# P8_CCD_CAM_BOARD_COMM.net
KiCad netlist of a schematic drawn in Altium Designer
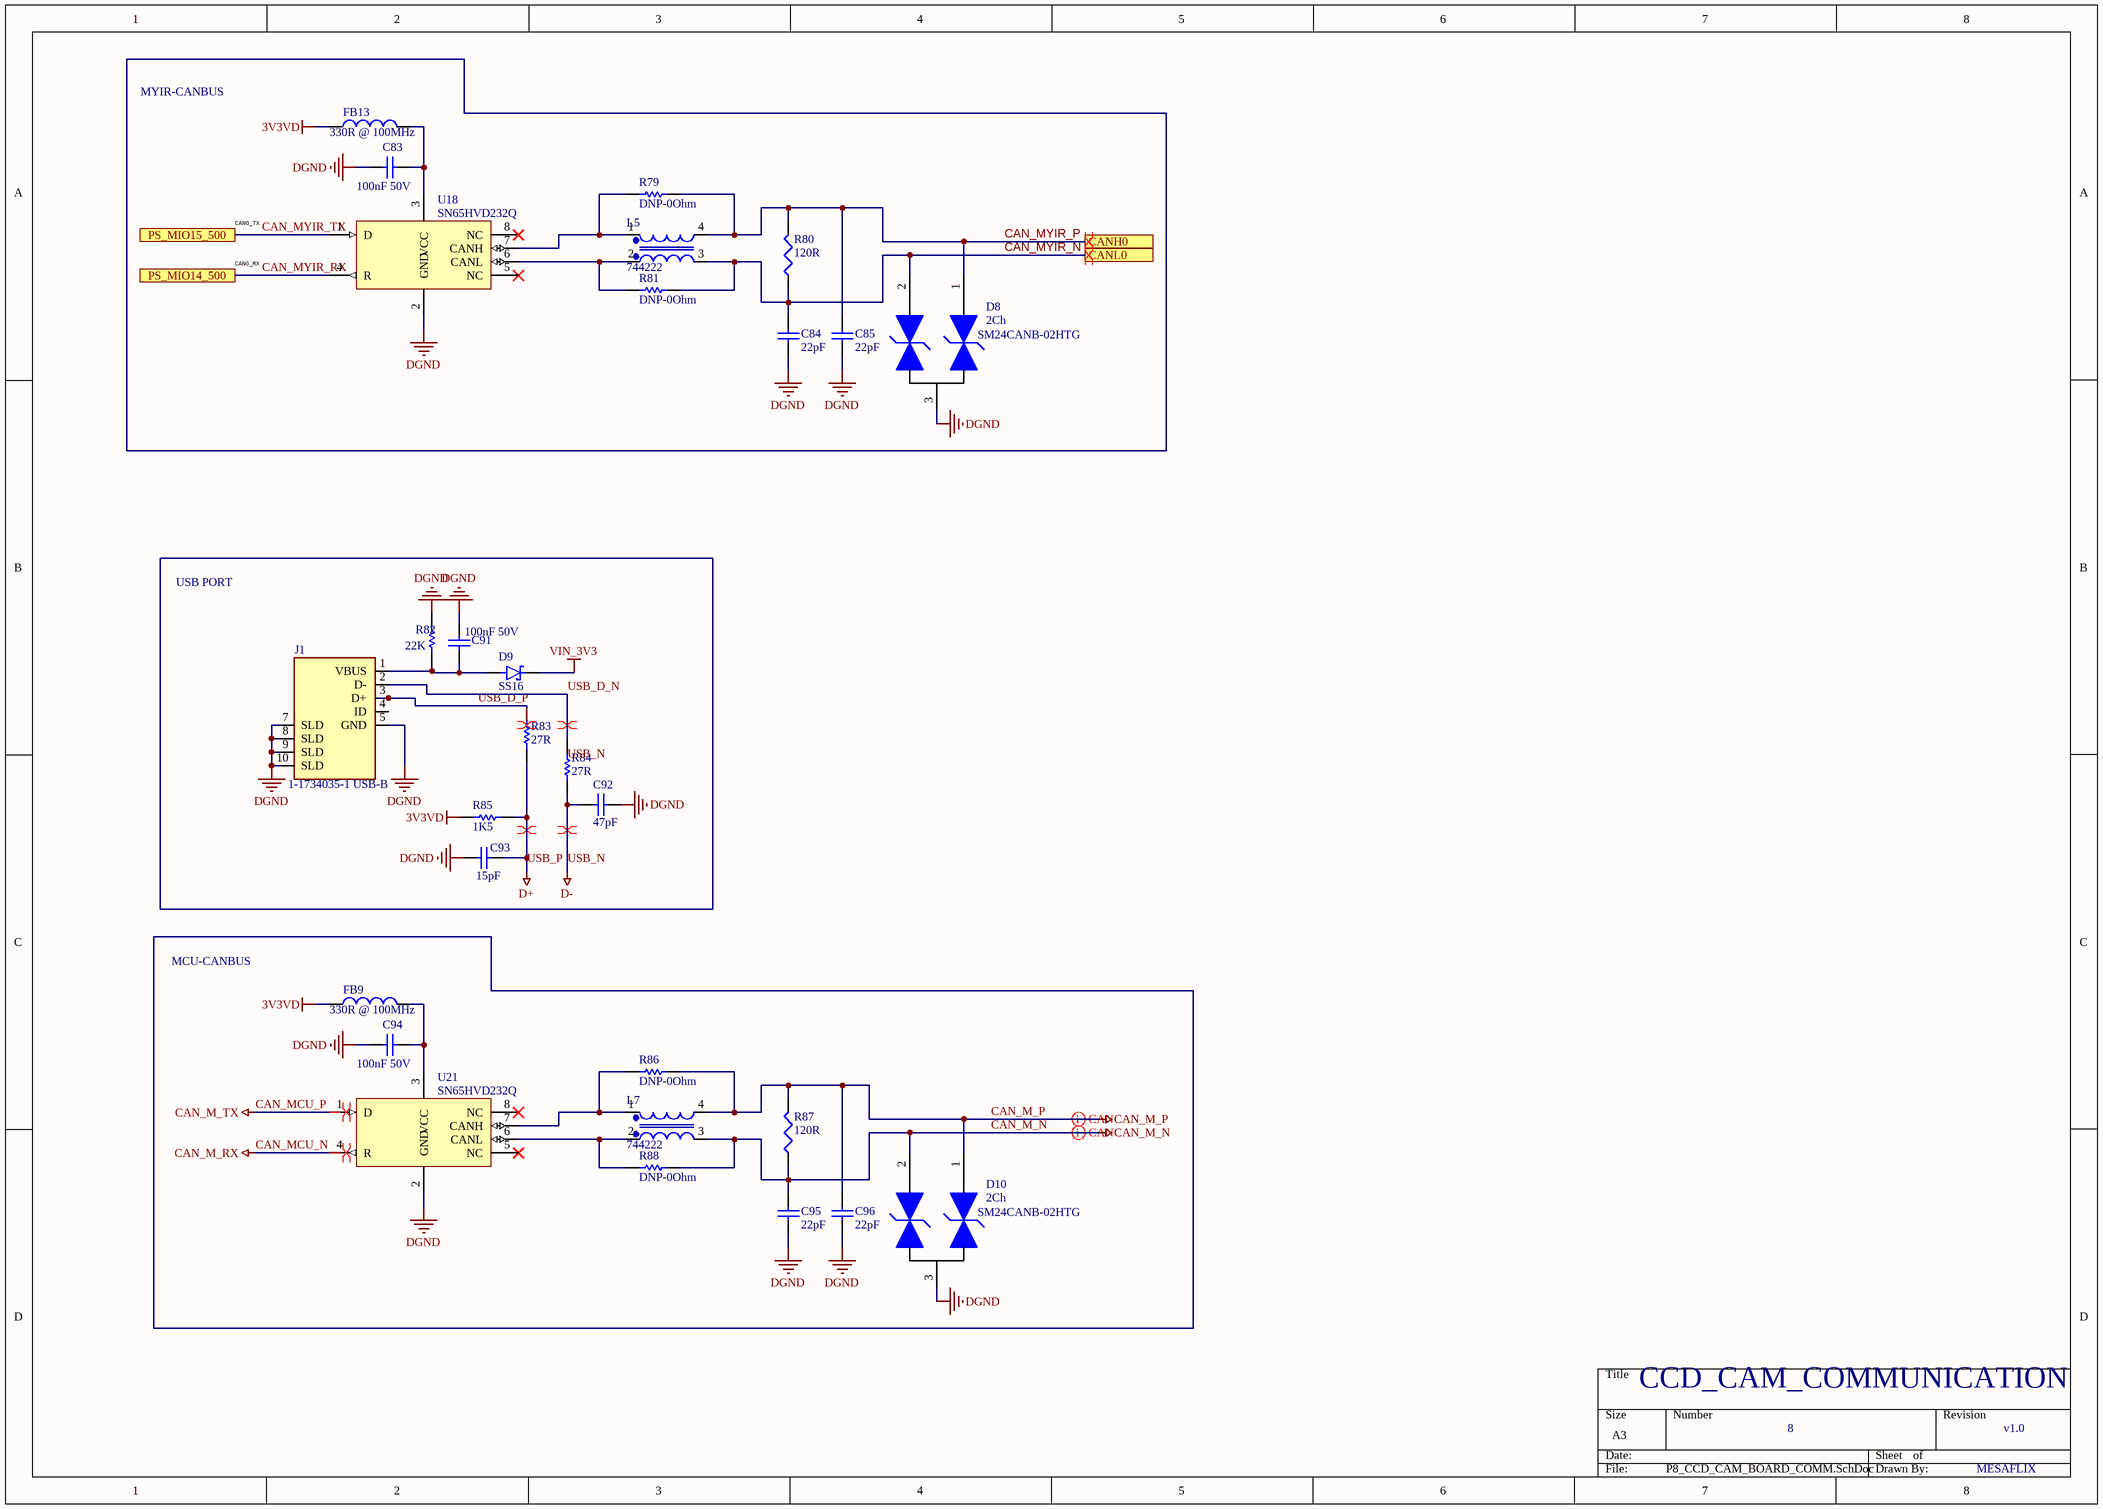
[diagram p0: P8_CCD_CAM_BOARD_COMM.SchDoc]

(export (version "E")
  (design (tool "Eeschema 10.0.6"))
  (components
    (comp (ref "C83")
      (value "100nF 50V")
      (footprint "CAP0603")
      (description "CAP CER 0.1UF 50V X7R 0603")
      (libsource (lib "CAP_Library") (part "CAP0603_100nF"))
    )
    (comp (ref "C84")
      (value "22pF")
      (footprint "CAP0603")
      (description "CAP CER 22PF 50V C0G/NP0 0603")
      (libsource (lib "CAP_Library") (part "CAP0603_22pF"))
    )
    (comp (ref "C85")
      (value "22pF")
      (footprint "CAP0603")
      (description "CAP CER 22PF 50V C0G/NP0 0603")
      (libsource (lib "CAP_Library") (part "CAP0603_22pF"))
    )
    (comp (ref "C91")
      (value "100nF 50V")
      (footprint "CAP0603")
      (description "CAP CER 0.1UF 50V X7R 0603")
      (libsource (lib "CAP_Library") (part "CAP0603_100nF"))
    )
    (comp (ref "C92")
      (value "47pF")
      (footprint "CAP0603")
      (description "CAP CER 47PF 50V C0G 0603")
      (fields
        (field (name "DIGIKEYPARTNUMBER") "445-5636-1-ND")
        (field (name "MANUFACTURER") "TDK Corporation")
      )
      (libsource (lib "CAP_Library") (part "CAP0603_15pF"))
    )
    (comp (ref "C93")
      (value "15pF")
      (footprint "CAP0603")
      (description "CAP CER 15PF 25V C0G/NP0 0603")
      (fields
        (field (name "DIGIKEYPARTNUMBER") "445-5630-1-ND")
        (field (name "MANUFACTURER") "TDK Corporation")
      )
      (libsource (lib "CAP_Library") (part "CAP0603_15pF"))
    )
    (comp (ref "C94")
      (value "100nF 50V")
      (footprint "CAP0603")
      (description "CAP CER 0.1UF 50V X7R 0603")
      (libsource (lib "CAP_Library") (part "CAP0603_100nF"))
    )
    (comp (ref "C95")
      (value "22pF")
      (footprint "CAP0603")
      (description "CAP CER 22PF 50V C0G/NP0 0603")
      (libsource (lib "CAP_Library") (part "CAP0603_22pF"))
    )
    (comp (ref "C96")
      (value "22pF")
      (footprint "CAP0603")
      (description "CAP CER 22PF 50V C0G/NP0 0603")
      (libsource (lib "CAP_Library") (part "CAP0603_22pF"))
    )
    (comp (ref "D8")
      (value "2Ch")
      (footprint "SOT23_3-DIODE")
      (description "TVS DIODE 24VWM 50VC SOT23-3")
      (fields (field (name "P/N") "SM24CANB-02HTG"))
      (libsource (lib "DIODE_Library") (part "SM24CANB-02HTG_TVS"))
    )
    (comp (ref "D9")
      (value "SS16")
      (footprint "DIOM5227X250N")
      (description "Diode Schottky 60V 1A Surface Mount SMA _DO-214AC_")
      (fields (field (name "MF") "ON Semiconductor") (field (name "MP") "SS16T3G"))
      (libsource (lib "SS16") (part "SS16"))
    )
    (comp (ref "D10")
      (value "2Ch")
      (footprint "SOT23_3-DIODE")
      (description "TVS DIODE 24VWM 50VC SOT23-3")
      (fields (field (name "P/N") "SM24CANB-02HTG"))
      (libsource (lib "DIODE_Library") (part "SM24CANB-02HTG_TVS"))
    )
    (comp (ref "FB9")
      (value "330R @ 100MHz")
      (footprint "FB0603")
      (description "FERRITE BEAD 330 OHM 0603 1LN")
      (libsource (lib "FB_Library") (part "FB0603_330R@100MHz"))
    )
    (comp (ref "FB13")
      (value "330R @ 100MHz")
      (footprint "FB0603")
      (description "FERRITE BEAD 330 OHM 0603 1LN")
      (libsource (lib "FB_Library") (part "FB0603_330R@100MHz"))
    )
    (comp (ref "J1")
      (value "1-1734035-1 USB-B")
      (footprint "TE_1-1734035-1-3D")
      (description "Conn Mini USB 2.0 Type B RCP 5 POS 0.8mm Solder RA SMD 5 Terminal 1 Port Tray")
      (fields (field (name "MP") "1-1734035-1") (field (name "MF") "TE Connectivity"))
      (libsource (lib "1-1734035-1") (part "1-1734035-1"))
    )
    (comp (ref "L5")
      (value "744222")
      (footprint "IND_744222_3D")
      (description "Würth CMC 1MH 800MA 2LN 6 KOHM SMD")
      (fields (field (name "DIGIKEY PART NUMBER") "732-1485-1-ND"))
      (libsource (lib "TESLA_PCB_LIB") (part "IND_744222"))
    )
    (comp (ref "L7")
      (value "744222")
      (footprint "IND_744222_3D")
      (description "Würth CMC 1MH 800MA 2LN 6 KOHM SMD")
      (fields (field (name "DIGIKEY PART NUMBER") "732-1485-1-ND"))
      (libsource (lib "TESLA_PCB_LIB") (part "IND_744222"))
    )
    (comp (ref "R79")
      (value "DNP-0Ohm")
      (footprint "RES0603")
      (fields
        (field (name "DIGIKEYPARTNUMBER") "311-0.0LDCT-ND")
        (field (name "MANUFACTURER") "Yageo")
        (field (name "MANUFACTURERPARTNUMBER") "AC0603FR-070RL")
      )
      (libsource (lib "TESLA_PCB_LIB") (part "RES_1K_0603"))
    )
    (comp (ref "R80")
      (value "120R")
      (footprint "RES0603")
      (description "RES SMD 120 OHM 1% 1/10W 0603")
      (libsource (lib "RES_Library") (part "RES0603_120R"))
    )
    (comp (ref "R81")
      (value "DNP-0Ohm")
      (footprint "RES0603")
      (fields
        (field (name "DIGIKEYPARTNUMBER") "311-0.0LDCT-ND")
        (field (name "MANUFACTURER") "Yageo")
        (field (name "MANUFACTURERPARTNUMBER") "AC0603FR-070RL")
      )
      (libsource (lib "TESLA_PCB_LIB") (part "RES_1K_0603"))
    )
    (comp (ref "R82")
      (value "22K")
      (footprint "RES0603")
      (fields
        (field (name "DIGIKEYPARTNUMBER") "311-22KLDCT-ND")
        (field (name "MANUFACTURER") "Yageo")
        (field (name "MANUFACTURERPARTNUMBER") "AC0603FR-0722KL")
      )
      (libsource (lib "TESLA_PCB_LIB") (part "RES_1K_0603"))
    )
    (comp (ref "R83")
      (value "27R")
      (footprint "RES0603")
      (description "RES SMD 27 OHM 1% 1/10W 0603")
      (fields (field (name "DIGIKEYPARTNUMBER") "311-27.0HRCT-ND") (field (name "MANUFACTURER") "Yageo"))
      (libsource (lib "TESLA_PCB_LIB") (part "RES_1K_0603"))
    )
    (comp (ref "R84")
      (value "27R")
      (footprint "RES0603")
      (description "RES SMD 27 OHM 1% 1/10W 0603")
      (fields (field (name "DIGIKEYPARTNUMBER") "311-27.0HRCT-ND") (field (name "MANUFACTURER") "Yageo"))
      (libsource (lib "TESLA_PCB_LIB") (part "RES_1K_0603"))
    )
    (comp (ref "R85")
      (value "1K5")
      (footprint "RES0603")
      (fields
        (field (name "DIGIKEYPARTNUMBER") "YAG3645CT-ND")
        (field (name "MANUFACTURER") "Yageo")
        (field (name "MANUFACTURERPARTNUMBER") "AC0603JR-071K5L")
      )
      (libsource (lib "TESLA_PCB_LIB") (part "RES_1K_0603"))
    )
    (comp (ref "R86")
      (value "DNP-0Ohm")
      (footprint "RES0603")
      (fields
        (field (name "DIGIKEYPARTNUMBER") "311-0.0LDCT-ND")
        (field (name "MANUFACTURER") "Yageo")
        (field (name "MANUFACTURERPARTNUMBER") "AC0603FR-070RL")
      )
      (libsource (lib "TESLA_PCB_LIB") (part "RES_1K_0603"))
    )
    (comp (ref "R87")
      (value "120R")
      (footprint "RES0603")
      (description "RES SMD 120 OHM 1% 1/10W 0603")
      (libsource (lib "RES_Library") (part "RES0603_120R"))
    )
    (comp (ref "R88")
      (value "DNP-0Ohm")
      (footprint "RES0603")
      (fields
        (field (name "DIGIKEYPARTNUMBER") "311-0.0LDCT-ND")
        (field (name "MANUFACTURER") "Yageo")
        (field (name "MANUFACTURERPARTNUMBER") "AC0603FR-070RL")
      )
      (libsource (lib "TESLA_PCB_LIB") (part "RES_1K_0603"))
    )
    (comp (ref "U18")
      (value "SN65HVD232Q")
      (footprint "SOIC8")
      (description "IC TRANSCEIVER HALF 1/1 8SOIC")
      (libsource (lib "IC_Library") (part "SN65HVD232QDRQ1_CAN"))
    )
    (comp (ref "U21")
      (value "SN65HVD232Q")
      (footprint "SOIC8")
      (description "IC TRANSCEIVER HALF 1/1 8SOIC")
      (libsource (lib "IC_Library") (part "SN65HVD232QDRQ1_CAN"))
    )
  )
  (nets
    (net (code "1") (name "/CAN_MYIR_N") (class "Default")
      (node (ref "C84") (pin "2") (pinfunction "2_2") (pintype "passive"))
      (node (ref "D8") (pin "2") (pinfunction "2_2") (pintype "passive"))
      (node (ref "L5") (pin "3") (pinfunction "3_3") (pintype "passive"))
      (node (ref "R80") (pin "1") (pinfunction "1_1") (pintype "passive"))
      (node (ref "R81") (pin "2") (pinfunction "2_2") (pintype "passive"))
    )
    (net (code "2") (name "/CAN_MYIR_P") (class "Default")
      (node (ref "C85") (pin "2") (pinfunction "2_2") (pintype "passive"))
      (node (ref "D8") (pin "1") (pinfunction "1_1") (pintype "passive"))
      (node (ref "L5") (pin "4") (pinfunction "4_4") (pintype "passive"))
      (node (ref "R79") (pin "2") (pinfunction "2_2") (pintype "passive"))
      (node (ref "R80") (pin "2") (pinfunction "2_2") (pintype "passive"))
    )
    (net (code "3") (name "/CAN_MYIR_RX") (class "Default")
      (node (ref "U18") (pin "4") (pinfunction "R_4") (pintype "output"))
    )
    (net (code "4") (name "/CAN_MYIR_TX") (class "Default")
      (node (ref "U18") (pin "1") (pinfunction "D_1") (pintype "input"))
    )
    (net (code "5") (name "/USB_D_N") (class "Default")
      (node (ref "J1") (pin "2") (pinfunction "D-_2") (pintype "passive"))
      (node (ref "R84") (pin "1") (pinfunction "1_1") (pintype "passive"))
    )
    (net (code "6") (name "/USB_D_P") (class "Default")
      (node (ref "J1") (pin "3") (pinfunction "D+_3") (pintype "passive"))
      (node (ref "R83") (pin "1") (pinfunction "1_1") (pintype "passive"))
    )
    (net (code "7") (name "3V3VD") (class "Default")
      (node (ref "FB13") (pin "1") (pinfunction "1_1") (pintype "passive"))
      (node (ref "FB9") (pin "1") (pinfunction "1_1") (pintype "passive"))
      (node (ref "R85") (pin "2") (pinfunction "2_2") (pintype "passive"))
    )
    (net (code "8") (name "CAN_M_N") (class "Default")
      (node (ref "C95") (pin "2") (pinfunction "2_2") (pintype "passive"))
      (node (ref "D10") (pin "2") (pinfunction "2_2") (pintype "passive"))
      (node (ref "L7") (pin "3") (pinfunction "3_3") (pintype "passive"))
      (node (ref "R87") (pin "1") (pinfunction "1_1") (pintype "passive"))
      (node (ref "R88") (pin "2") (pinfunction "2_2") (pintype "passive"))
    )
    (net (code "9") (name "CAN_M_P") (class "Default")
      (node (ref "C96") (pin "2") (pinfunction "2_2") (pintype "passive"))
      (node (ref "D10") (pin "1") (pinfunction "1_1") (pintype "passive"))
      (node (ref "L7") (pin "4") (pinfunction "4_4") (pintype "passive"))
      (node (ref "R86") (pin "2") (pinfunction "2_2") (pintype "passive"))
      (node (ref "R87") (pin "2") (pinfunction "2_2") (pintype "passive"))
    )
    (net (code "10") (name "CAN_M_RX") (class "Default")
      (node (ref "U21") (pin "4") (pinfunction "R_4") (pintype "output"))
    )
    (net (code "11") (name "CAN_M_TX") (class "Default")
      (node (ref "U21") (pin "1") (pinfunction "D_1") (pintype "input"))
    )
    (net (code "12") (name "D+") (class "Default")
      (node (ref "C93") (pin "1") (pinfunction "1_1") (pintype "passive"))
      (node (ref "R83") (pin "2") (pinfunction "2_2") (pintype "passive"))
      (node (ref "R85") (pin "1") (pinfunction "1_1") (pintype "passive"))
    )
    (net (code "13") (name "D-") (class "Default")
      (node (ref "C92") (pin "1") (pinfunction "1_1") (pintype "passive"))
      (node (ref "R84") (pin "2") (pinfunction "2_2") (pintype "passive"))
    )
    (net (code "14") (name "DGND") (class "Default")
      (node (ref "C83") (pin "1") (pinfunction "1_1") (pintype "passive"))
      (node (ref "C84") (pin "1") (pinfunction "1_1") (pintype "passive"))
      (node (ref "C85") (pin "1") (pinfunction "1_1") (pintype "passive"))
      (node (ref "C91") (pin "2") (pinfunction "2_2") (pintype "passive"))
      (node (ref "C92") (pin "2") (pinfunction "2_2") (pintype "passive"))
      (node (ref "C93") (pin "2") (pinfunction "2_2") (pintype "passive"))
      (node (ref "C94") (pin "1") (pinfunction "1_1") (pintype "passive"))
      (node (ref "C95") (pin "1") (pinfunction "1_1") (pintype "passive"))
      (node (ref "C96") (pin "1") (pinfunction "1_1") (pintype "passive"))
      (node (ref "D10") (pin "3") (pinfunction "3_3") (pintype "passive"))
      (node (ref "D8") (pin "3") (pinfunction "3_3") (pintype "passive"))
      (node (ref "J1") (pin "10") (pinfunction "SLD_10") (pintype "passive"))
      (node (ref "J1") (pin "5") (pinfunction "GND_5") (pintype "passive"))
      (node (ref "J1") (pin "7") (pinfunction "SLD_7") (pintype "passive"))
      (node (ref "J1") (pin "8") (pinfunction "SLD_8") (pintype "passive"))
      (node (ref "J1") (pin "9") (pinfunction "SLD_9") (pintype "passive"))
      (node (ref "R82") (pin "2") (pinfunction "2_2") (pintype "passive"))
      (node (ref "U18") (pin "2") (pinfunction "GND_2") (pintype "power_in"))
      (node (ref "U21") (pin "2") (pinfunction "GND_2") (pintype "power_in"))
    )
    (net (code "15") (name "Net-(J1-VBUS)") (class "Default")
      (node (ref "C91") (pin "1") (pinfunction "1_1") (pintype "passive"))
      (node (ref "D9") (pin "A") (pinfunction "A_A") (pintype "passive"))
      (node (ref "J1") (pin "1") (pinfunction "VBUS_1") (pintype "passive"))
      (node (ref "R82") (pin "1") (pinfunction "1_1") (pintype "passive"))
    )
    (net (code "16") (name "Net-(U18-CANH)") (class "Default")
      (node (ref "L5") (pin "1") (pinfunction "1_1") (pintype "passive"))
      (node (ref "R79") (pin "1") (pinfunction "1_1") (pintype "passive"))
      (node (ref "U18") (pin "7") (pinfunction "CANH_7") (pintype "bidirectional"))
    )
    (net (code "17") (name "Net-(U18-CANL)") (class "Default")
      (node (ref "L5") (pin "2") (pinfunction "2_2") (pintype "passive"))
      (node (ref "R81") (pin "1") (pinfunction "1_1") (pintype "passive"))
      (node (ref "U18") (pin "6") (pinfunction "CANL_6") (pintype "bidirectional"))
    )
    (net (code "18") (name "Net-(U18-VCC)") (class "Default")
      (node (ref "C83") (pin "2") (pinfunction "2_2") (pintype "passive"))
      (node (ref "FB13") (pin "2") (pinfunction "2_2") (pintype "passive"))
      (node (ref "U18") (pin "3") (pinfunction "VCC_3") (pintype "power_in"))
    )
    (net (code "19") (name "Net-(U21-CANH)") (class "Default")
      (node (ref "L7") (pin "1") (pinfunction "1_1") (pintype "passive"))
      (node (ref "R86") (pin "1") (pinfunction "1_1") (pintype "passive"))
      (node (ref "U21") (pin "7") (pinfunction "CANH_7") (pintype "bidirectional"))
    )
    (net (code "20") (name "Net-(U21-CANL)") (class "Default")
      (node (ref "L7") (pin "2") (pinfunction "2_2") (pintype "passive"))
      (node (ref "R88") (pin "1") (pinfunction "1_1") (pintype "passive"))
      (node (ref "U21") (pin "6") (pinfunction "CANL_6") (pintype "bidirectional"))
    )
    (net (code "21") (name "Net-(U21-VCC)") (class "Default")
      (node (ref "C94") (pin "2") (pinfunction "2_2") (pintype "passive"))
      (node (ref "FB9") (pin "2") (pinfunction "2_2") (pintype "passive"))
      (node (ref "U21") (pin "3") (pinfunction "VCC_3") (pintype "power_in"))
    )
    (net (code "22") (name "VIN_3V3") (class "Default")
      (node (ref "D9") (pin "C") (pinfunction "K_C") (pintype "passive"))
    )
    (net (code "23") (name "unconnected-(J1-ID-Pad4)") (class "Default")
      (node (ref "J1") (pin "4") (pinfunction "ID_4") (pintype "passive"))
    )
    (net (code "24") (name "unconnected-(U18-NC-Pad5)") (class "Default")
      (node (ref "U18") (pin "5") (pinfunction "NC_5") (pintype "passive+no_connect"))
    )
    (net (code "25") (name "unconnected-(U18-NC-Pad8)") (class "Default")
      (node (ref "U18") (pin "8") (pinfunction "NC_8") (pintype "passive+no_connect"))
    )
    (net (code "26") (name "unconnected-(U21-NC-Pad5)") (class "Default")
      (node (ref "U21") (pin "5") (pinfunction "NC_5") (pintype "passive+no_connect"))
    )
    (net (code "27") (name "unconnected-(U21-NC-Pad8)") (class "Default")
      (node (ref "U21") (pin "8") (pinfunction "NC_8") (pintype "passive+no_connect"))
    )
  )
)
